# BMP280.net
KiCad netlist of a schematic drawn in Altium Designer
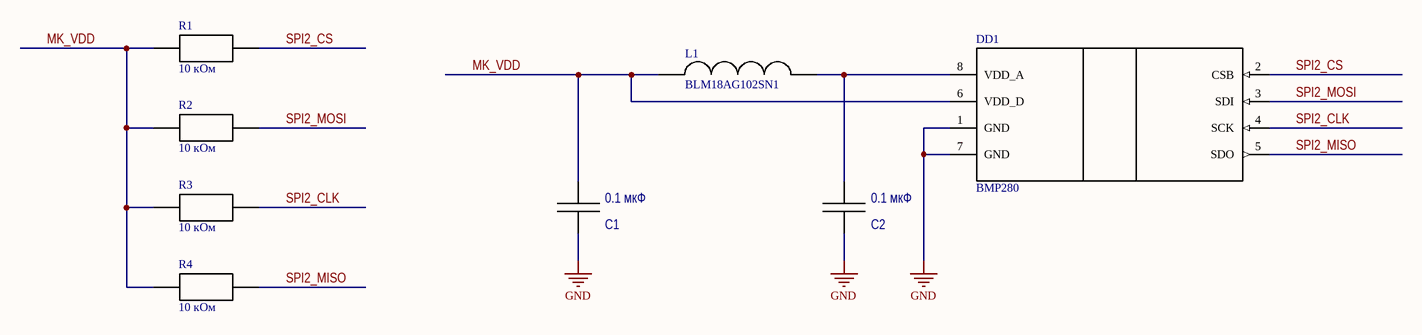
[diagram p0: BMP280.SchDoc]

(export (version "E")
  (design (tool "Eeschema 10.0.6"))
  (components
    (comp (ref "C1")
      (value "0.1 мкФ")
      (footprint "C 1206")
      (description "SMD Capacitor 1206")
      (fields
        (field (name "TOLERANCE") "/Укажите допуск в процентах/")
        (field (name "MANUFACTURER") "/Укажите компанию-производителя/")
      )
      (libsource (lib "my_lib") (part "CAP 1206"))
    )
    (comp (ref "C2")
      (value "0.1 мкФ")
      (footprint "C 1206")
      (description "SMD Capacitor 1206")
      (fields
        (field (name "TOLERANCE") "/Укажите допуск в процентах/")
        (field (name "MANUFACTURER") "/Укажите компанию-производителя/")
      )
      (libsource (lib "my_lib") (part "CAP 1206"))
    )
    (comp (ref "DD1")
      (value "BMP280")
      (footprint "LGA_2.0_2.5_8PIN")
      (libsource (lib "my_lib") (part "BMP280"))
    )
    (comp (ref "L1")
      (value "BLM18AG102SN1")
      (footprint "FB 0603")
      (libsource (lib "my_lib") (part "BLM18AG102SN1"))
    )
    (comp (ref "R1") (value "10 кОм") (footprint "RES 0805") (libsource (lib "my_lib") (part "RES 0805")))
    (comp (ref "R2") (value "10 кОм") (footprint "RES 0805") (libsource (lib "my_lib") (part "RES 0805")))
    (comp (ref "R3") (value "10 кОм") (footprint "RES 0805") (libsource (lib "my_lib") (part "RES 0805")))
    (comp (ref "R4") (value "10 кОм") (footprint "RES 0805") (libsource (lib "my_lib") (part "RES 0805")))
  )
  (nets
    (net (code "1") (name "/MK_VDD") (class "Default")
      (node (ref "C1") (pin "1") (pinfunction "1_1") (pintype "passive"))
      (node (ref "DD1") (pin "6") (pinfunction "VDD_D_6") (pintype "power_in"))
      (node (ref "L1") (pin "1") (pinfunction "1_1") (pintype "passive"))
      (node (ref "R1") (pin "1") (pinfunction "1_1") (pintype "passive"))
      (node (ref "R2") (pin "1") (pinfunction "1_1") (pintype "passive"))
      (node (ref "R3") (pin "1") (pinfunction "1_1") (pintype "passive"))
      (node (ref "R4") (pin "1") (pinfunction "1_1") (pintype "passive"))
    )
    (net (code "2") (name "/SPI2_CLK") (class "Default")
      (node (ref "DD1") (pin "4") (pinfunction "SCK_4") (pintype "input"))
      (node (ref "R3") (pin "2") (pinfunction "2_2") (pintype "passive"))
    )
    (net (code "3") (name "/SPI2_CS") (class "Default")
      (node (ref "DD1") (pin "2") (pinfunction "CSB_2") (pintype "input"))
      (node (ref "R1") (pin "2") (pinfunction "2_2") (pintype "passive"))
    )
    (net (code "4") (name "/SPI2_MISO") (class "Default")
      (node (ref "DD1") (pin "5") (pinfunction "SDO_5") (pintype "output"))
      (node (ref "R4") (pin "2") (pinfunction "2_2") (pintype "passive"))
    )
    (net (code "5") (name "/SPI2_MOSI") (class "Default")
      (node (ref "DD1") (pin "3") (pinfunction "SDI_3") (pintype "input"))
      (node (ref "R2") (pin "2") (pinfunction "2_2") (pintype "passive"))
    )
    (net (code "6") (name "GND") (class "Default")
      (node (ref "C1") (pin "2") (pinfunction "2_2") (pintype "passive"))
      (node (ref "C2") (pin "2") (pinfunction "2_2") (pintype "passive"))
      (node (ref "DD1") (pin "1") (pinfunction "GND_1") (pintype "power_in"))
      (node (ref "DD1") (pin "7") (pinfunction "GND_7") (pintype "power_in"))
    )
    (net (code "7") (name "Net-(DD1-VDD_A)") (class "Default")
      (node (ref "C2") (pin "1") (pinfunction "1_1") (pintype "passive"))
      (node (ref "DD1") (pin "8") (pinfunction "VDD_A_8") (pintype "power_in"))
      (node (ref "L1") (pin "2") (pinfunction "2_2") (pintype "passive"))
    )
  )
)
